# PGTNX02_vca.net
KiCad netlist of a schematic drawn in EAGLE
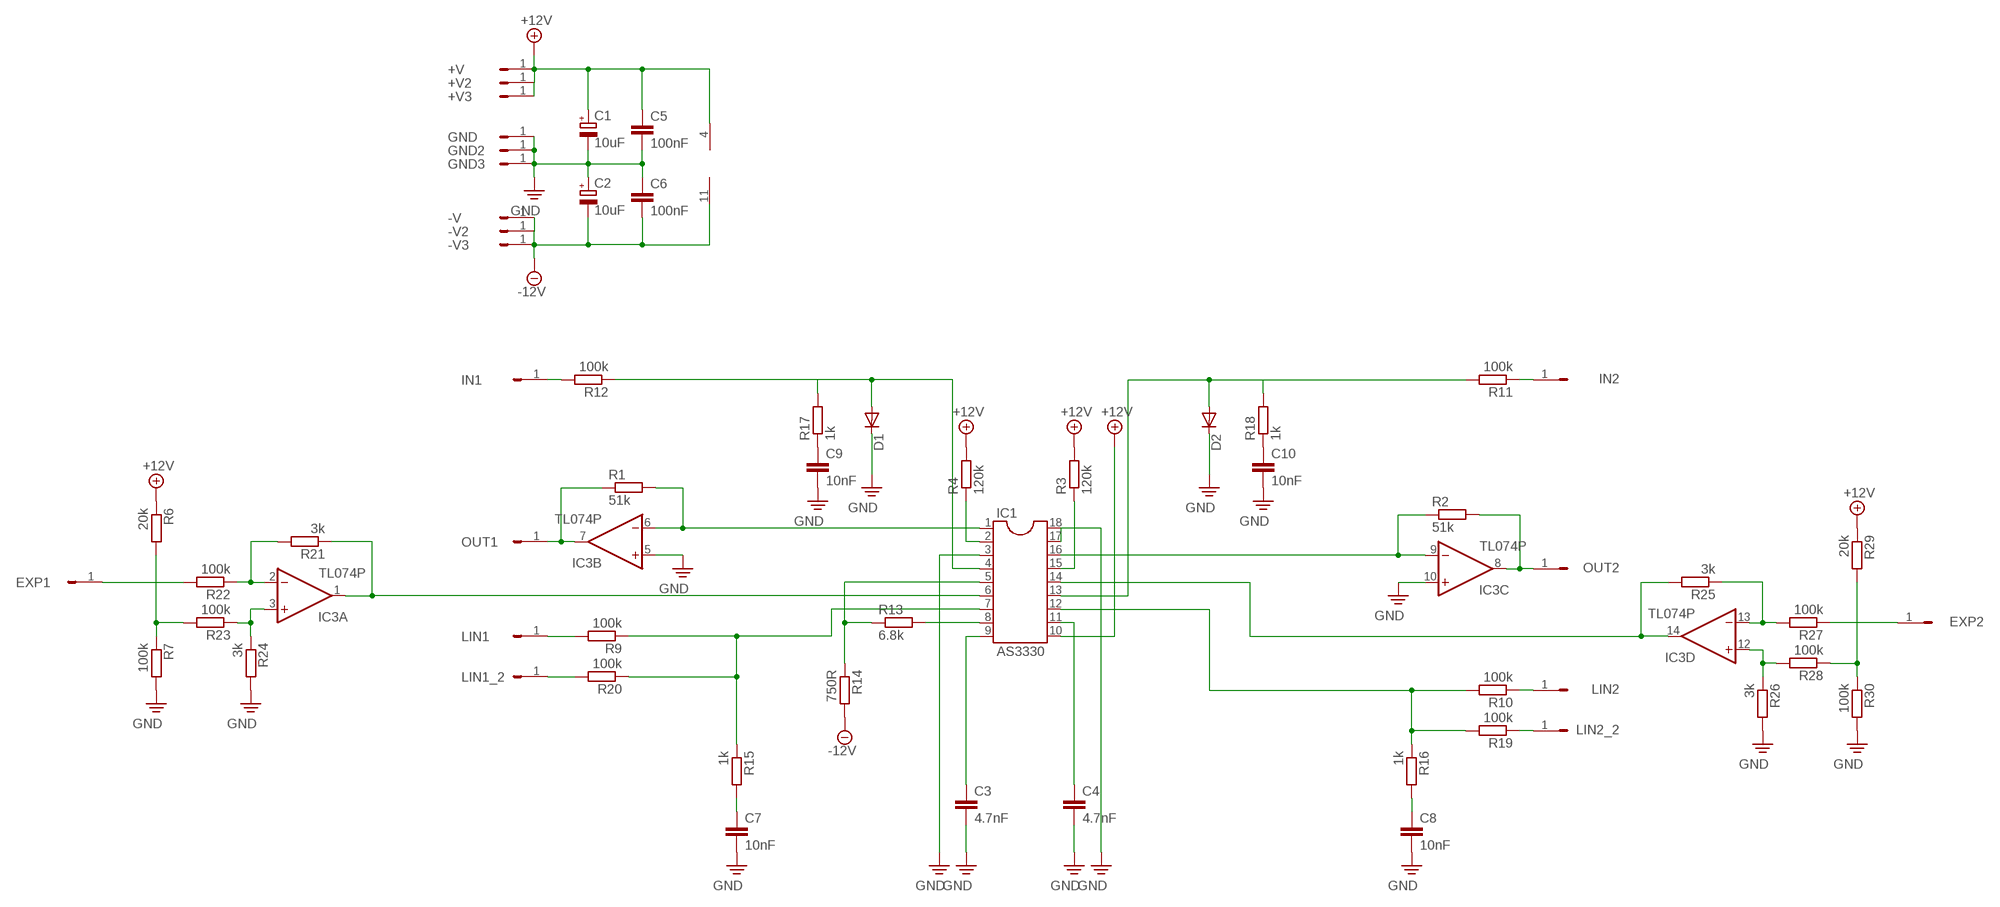
[diagram p0: schematic, sheet 1]

(export (version "E")
  (design (tool "Eeschema 10.0.6"))
  (components
    (comp (ref "+V")
      (value "HEADER/MALE/01")
      (footprint "eagle-import:HEADER_MALE_01")
      (fields (field (name "SPICEPREFIX") "X"))
      (libsource (lib "eagle-import") (part "HEADER/MALE/01"))
    )
    (comp (ref "+V2")
      (value "HEADER/MALE/01")
      (footprint "eagle-import:HEADER_MALE_01")
      (fields (field (name "SPICEPREFIX") "X"))
      (libsource (lib "eagle-import") (part "HEADER/MALE/01"))
    )
    (comp (ref "+V3")
      (value "HEADER/MALE/01")
      (footprint "eagle-import:HEADER_MALE_01")
      (fields (field (name "SPICEPREFIX") "X"))
      (libsource (lib "eagle-import") (part "HEADER/MALE/01"))
    )
    (comp (ref "-V")
      (value "HEADER/MALE/01")
      (footprint "eagle-import:HEADER_MALE_01")
      (fields (field (name "SPICEPREFIX") "X"))
      (libsource (lib "eagle-import") (part "HEADER/MALE/01"))
    )
    (comp (ref "-V2")
      (value "HEADER/MALE/01")
      (footprint "eagle-import:HEADER_MALE_01")
      (fields (field (name "SPICEPREFIX") "X"))
      (libsource (lib "eagle-import") (part "HEADER/MALE/01"))
    )
    (comp (ref "-V3")
      (value "HEADER/MALE/01")
      (footprint "eagle-import:HEADER_MALE_01")
      (fields (field (name "SPICEPREFIX") "X"))
      (libsource (lib "eagle-import") (part "HEADER/MALE/01"))
    )
    (comp (ref "C1")
      (value "10uF")
      (footprint "eagle-import:E2,5-6")
      (fields (field (name "SPICEPREFIX") "C"))
      (libsource (lib "eagle-import") (part "CAPACITOR/POLARIZEDE2.5-6"))
    )
    (comp (ref "C2")
      (value "10uF")
      (footprint "eagle-import:E2,5-6")
      (fields (field (name "SPICEPREFIX") "C"))
      (libsource (lib "eagle-import") (part "CAPACITOR/POLARIZEDE2.5-6"))
    )
    (comp (ref "C3")
      (value "4.7nF")
      (footprint "eagle-import:CERAMICDISC_5")
      (libsource (lib "eagle-import") (part "CAPACITORCERAMICDISC/5"))
    )
    (comp (ref "C4")
      (value "4.7nF")
      (footprint "eagle-import:CERAMICDISC_5")
      (libsource (lib "eagle-import") (part "CAPACITORCERAMICDISC/5"))
    )
    (comp (ref "C5")
      (value "100nF")
      (footprint "eagle-import:CERAMICDISC_5")
      (libsource (lib "eagle-import") (part "CAPACITORCERAMICDISC/5"))
    )
    (comp (ref "C6")
      (value "100nF")
      (footprint "eagle-import:CERAMICDISC_5")
      (libsource (lib "eagle-import") (part "CAPACITORCERAMICDISC/5"))
    )
    (comp (ref "C7")
      (value "10nF")
      (footprint "eagle-import:CERAMICDISC_5")
      (libsource (lib "eagle-import") (part "CAPACITORCERAMICDISC/5"))
    )
    (comp (ref "C8")
      (value "10nF")
      (footprint "eagle-import:CERAMICDISC_5")
      (libsource (lib "eagle-import") (part "CAPACITORCERAMICDISC/5"))
    )
    (comp (ref "C9")
      (value "10nF")
      (footprint "eagle-import:CERAMICDISC_5")
      (libsource (lib "eagle-import") (part "CAPACITORCERAMICDISC/5"))
    )
    (comp (ref "C10")
      (value "10nF")
      (footprint "eagle-import:CERAMICDISC_5")
      (libsource (lib "eagle-import") (part "CAPACITORCERAMICDISC/5"))
    )
    (comp (ref "D1")
      (value "1N4148DO35-7")
      (footprint "eagle-import:DO35-7")
      (libsource (lib "eagle-import") (part "1N4148DO35-7"))
    )
    (comp (ref "D2")
      (value "1N4148DO35-7")
      (footprint "eagle-import:DO35-7")
      (libsource (lib "eagle-import") (part "1N4148DO35-7"))
    )
    (comp (ref "EXP1")
      (value "HEADER/MALE/01")
      (footprint "eagle-import:HEADER_MALE_01")
      (libsource (lib "eagle-import") (part "HEADER/MALE/01"))
    )
    (comp (ref "EXP2")
      (value "HEADER/MALE/01")
      (footprint "eagle-import:HEADER_MALE_01")
      (libsource (lib "eagle-import") (part "HEADER/MALE/01"))
    )
    (comp (ref "GND")
      (value "HEADER/MALE/01")
      (footprint "eagle-import:HEADER_MALE_01")
      (fields (field (name "SPICEPREFIX") "X"))
      (libsource (lib "eagle-import") (part "HEADER/MALE/01"))
    )
    (comp (ref "GND2")
      (value "HEADER/MALE/01")
      (footprint "eagle-import:HEADER_MALE_01")
      (fields (field (name "SPICEPREFIX") "X"))
      (libsource (lib "eagle-import") (part "HEADER/MALE/01"))
    )
    (comp (ref "GND3")
      (value "HEADER/MALE/01")
      (footprint "eagle-import:HEADER_MALE_01")
      (fields (field (name "SPICEPREFIX") "X"))
      (libsource (lib "eagle-import") (part "HEADER/MALE/01"))
    )
    (comp (ref "IC1")
      (value "AS3330")
      (footprint "eagle-import:DIL18")
      (libsource (lib "eagle-import") (part "DIL18"))
    )
    (comp (ref "IC3")
      (value "TL074P")
      (footprint "eagle-import:DIL14")
      (libsource (lib "eagle-import") (part "TL074P"))
    )
    (comp (ref "IN1")
      (value "HEADER/MALE/01")
      (footprint "eagle-import:HEADER_MALE_01")
      (libsource (lib "eagle-import") (part "HEADER/MALE/01"))
    )
    (comp (ref "IN2")
      (value "HEADER/MALE/01")
      (footprint "eagle-import:HEADER_MALE_01")
      (libsource (lib "eagle-import") (part "HEADER/MALE/01"))
    )
    (comp (ref "LIN1")
      (value "HEADER/MALE/01")
      (footprint "eagle-import:HEADER_MALE_01")
      (libsource (lib "eagle-import") (part "HEADER/MALE/01"))
    )
    (comp (ref "LIN1_2")
      (value "HEADER/MALE/01")
      (footprint "eagle-import:HEADER_MALE_01")
      (libsource (lib "eagle-import") (part "HEADER/MALE/01"))
    )
    (comp (ref "LIN2")
      (value "HEADER/MALE/01")
      (footprint "eagle-import:HEADER_MALE_01")
      (libsource (lib "eagle-import") (part "HEADER/MALE/01"))
    )
    (comp (ref "LIN2_2")
      (value "HEADER/MALE/01")
      (footprint "eagle-import:HEADER_MALE_01")
      (libsource (lib "eagle-import") (part "HEADER/MALE/01"))
    )
    (comp (ref "OUT1")
      (value "HEADER/MALE/01")
      (footprint "eagle-import:HEADER_MALE_01")
      (libsource (lib "eagle-import") (part "HEADER/MALE/01"))
    )
    (comp (ref "OUT2")
      (value "HEADER/MALE/01")
      (footprint "eagle-import:HEADER_MALE_01")
      (libsource (lib "eagle-import") (part "HEADER/MALE/01"))
    )
    (comp (ref "R1")
      (value "51k")
      (footprint "eagle-import:RESISTOR_7.5")
      (libsource (lib "eagle-import") (part "RESISTORRESISTOR/UPRIGHT/7.5"))
    )
    (comp (ref "R2")
      (value "51k")
      (footprint "eagle-import:RESISTOR_7.5")
      (libsource (lib "eagle-import") (part "RESISTORRESISTOR/UPRIGHT/7.5"))
    )
    (comp (ref "R3")
      (value "120k")
      (footprint "eagle-import:RESISTOR_7.5")
      (libsource (lib "eagle-import") (part "RESISTORRESISTOR/UPRIGHT/7.5"))
    )
    (comp (ref "R4")
      (value "120k")
      (footprint "eagle-import:RESISTOR_7.5")
      (libsource (lib "eagle-import") (part "RESISTORRESISTOR/UPRIGHT/7.5"))
    )
    (comp (ref "R6")
      (value "20k")
      (footprint "eagle-import:RESISTOR_7.5")
      (libsource (lib "eagle-import") (part "RESISTORRESISTOR/UPRIGHT/7.5"))
    )
    (comp (ref "R7")
      (value "100k")
      (footprint "eagle-import:RESISTOR_7.5")
      (libsource (lib "eagle-import") (part "RESISTORRESISTOR/UPRIGHT/7.5"))
    )
    (comp (ref "R9")
      (value "100k")
      (footprint "eagle-import:RESISTOR_7.5")
      (libsource (lib "eagle-import") (part "RESISTORRESISTOR/UPRIGHT/7.5"))
    )
    (comp (ref "R10")
      (value "100k")
      (footprint "eagle-import:RESISTOR_7.5")
      (libsource (lib "eagle-import") (part "RESISTORRESISTOR/UPRIGHT/7.5"))
    )
    (comp (ref "R11")
      (value "100k")
      (footprint "eagle-import:RESISTOR_7.5")
      (libsource (lib "eagle-import") (part "RESISTORRESISTOR/UPRIGHT/7.5"))
    )
    (comp (ref "R12")
      (value "100k")
      (footprint "eagle-import:RESISTOR_7.5")
      (libsource (lib "eagle-import") (part "RESISTORRESISTOR/UPRIGHT/7.5"))
    )
    (comp (ref "R13")
      (value "6.8k")
      (footprint "eagle-import:RESISTOR_7.5")
      (libsource (lib "eagle-import") (part "RESISTORRESISTOR/UPRIGHT/7.5"))
    )
    (comp (ref "R14")
      (value "750R")
      (footprint "eagle-import:RESISTOR_7.5")
      (libsource (lib "eagle-import") (part "RESISTORRESISTOR/UPRIGHT/7.5"))
    )
    (comp (ref "R15")
      (value "1k")
      (footprint "eagle-import:RESISTOR_7.5")
      (libsource (lib "eagle-import") (part "RESISTORRESISTOR/UPRIGHT/7.5"))
    )
    (comp (ref "R16")
      (value "1k")
      (footprint "eagle-import:RESISTOR_7.5")
      (libsource (lib "eagle-import") (part "RESISTORRESISTOR/UPRIGHT/7.5"))
    )
    (comp (ref "R17")
      (value "1k")
      (footprint "eagle-import:RESISTOR_7.5")
      (libsource (lib "eagle-import") (part "RESISTORRESISTOR/UPRIGHT/7.5"))
    )
    (comp (ref "R18")
      (value "1k")
      (footprint "eagle-import:RESISTOR_7.5")
      (libsource (lib "eagle-import") (part "RESISTORRESISTOR/UPRIGHT/7.5"))
    )
    (comp (ref "R19")
      (value "100k")
      (footprint "eagle-import:RESISTOR_7.5")
      (libsource (lib "eagle-import") (part "RESISTORRESISTOR/UPRIGHT/7.5"))
    )
    (comp (ref "R20")
      (value "100k")
      (footprint "eagle-import:RESISTOR_7.5")
      (libsource (lib "eagle-import") (part "RESISTORRESISTOR/UPRIGHT/7.5"))
    )
    (comp (ref "R21")
      (value "3k")
      (footprint "eagle-import:RESISTOR_7.5")
      (libsource (lib "eagle-import") (part "RESISTORRESISTOR/UPRIGHT/7.5"))
    )
    (comp (ref "R22")
      (value "100k")
      (footprint "eagle-import:RESISTOR_7.5")
      (libsource (lib "eagle-import") (part "RESISTORRESISTOR/UPRIGHT/7.5"))
    )
    (comp (ref "R23")
      (value "100k")
      (footprint "eagle-import:RESISTOR_7.5")
      (libsource (lib "eagle-import") (part "RESISTORRESISTOR/UPRIGHT/7.5"))
    )
    (comp (ref "R24")
      (value "3k")
      (footprint "eagle-import:RESISTOR_7.5")
      (libsource (lib "eagle-import") (part "RESISTORRESISTOR/UPRIGHT/7.5"))
    )
    (comp (ref "R25")
      (value "3k")
      (footprint "eagle-import:RESISTOR_7.5")
      (libsource (lib "eagle-import") (part "RESISTORRESISTOR/UPRIGHT/7.5"))
    )
    (comp (ref "R26")
      (value "3k")
      (footprint "eagle-import:RESISTOR_7.5")
      (libsource (lib "eagle-import") (part "RESISTORRESISTOR/UPRIGHT/7.5"))
    )
    (comp (ref "R27")
      (value "100k")
      (footprint "eagle-import:RESISTOR_7.5")
      (libsource (lib "eagle-import") (part "RESISTORRESISTOR/UPRIGHT/7.5"))
    )
    (comp (ref "R28")
      (value "100k")
      (footprint "eagle-import:RESISTOR_7.5")
      (libsource (lib "eagle-import") (part "RESISTORRESISTOR/UPRIGHT/7.5"))
    )
    (comp (ref "R29")
      (value "20k")
      (footprint "eagle-import:RESISTOR_7.5")
      (libsource (lib "eagle-import") (part "RESISTORRESISTOR/UPRIGHT/7.5"))
    )
    (comp (ref "R30")
      (value "100k")
      (footprint "eagle-import:RESISTOR_7.5")
      (libsource (lib "eagle-import") (part "RESISTORRESISTOR/UPRIGHT/7.5"))
    )
  )
  (nets
    (net (code "1") (name "+12V") (class "Default")
      (node (ref "+V") (pin "1") (pinfunction "3_1") (pintype "passive"))
      (node (ref "+V2") (pin "1") (pinfunction "3_1") (pintype "passive"))
      (node (ref "+V3") (pin "1") (pinfunction "3_1") (pintype "passive"))
      (node (ref "C1") (pin "+") (pinfunction "+_+") (pintype "passive"))
      (node (ref "C5") (pin "1") (pinfunction "1_1") (pintype "passive"))
      (node (ref "IC1") (pin "10") (pinfunction "10_10") (pintype "passive"))
      (node (ref "IC3") (pin "4") (pinfunction "V+_4") (pintype "power_in"))
      (node (ref "R29") (pin "1") (pinfunction "1_1") (pintype "passive"))
      (node (ref "R3") (pin "2") (pinfunction "2_2") (pintype "passive"))
      (node (ref "R4") (pin "2") (pinfunction "2_2") (pintype "passive"))
      (node (ref "R6") (pin "1") (pinfunction "1_1") (pintype "passive"))
    )
    (net (code "2") (name "-12V") (class "Default")
      (node (ref "-V") (pin "1") (pinfunction "3_1") (pintype "passive"))
      (node (ref "-V2") (pin "1") (pinfunction "3_1") (pintype "passive"))
      (node (ref "-V3") (pin "1") (pinfunction "3_1") (pintype "passive"))
      (node (ref "C2") (pin "-") (pinfunction "-_-") (pintype "passive"))
      (node (ref "C6") (pin "2") (pinfunction "2_2") (pintype "passive"))
      (node (ref "IC3") (pin "11") (pinfunction "V-_11") (pintype "power_in"))
      (node (ref "R14") (pin "2") (pinfunction "2_2") (pintype "passive"))
    )
    (net (code "3") (name "GND") (class "Default")
      (node (ref "C1") (pin "-") (pinfunction "-_-") (pintype "passive"))
      (node (ref "C10") (pin "2") (pinfunction "2_2") (pintype "passive"))
      (node (ref "C2") (pin "+") (pinfunction "+_+") (pintype "passive"))
      (node (ref "C3") (pin "2") (pinfunction "2_2") (pintype "passive"))
      (node (ref "C4") (pin "2") (pinfunction "2_2") (pintype "passive"))
      (node (ref "C5") (pin "2") (pinfunction "2_2") (pintype "passive"))
      (node (ref "C6") (pin "1") (pinfunction "1_1") (pintype "passive"))
      (node (ref "C7") (pin "2") (pinfunction "2_2") (pintype "passive"))
      (node (ref "C8") (pin "2") (pinfunction "2_2") (pintype "passive"))
      (node (ref "C9") (pin "2") (pinfunction "2_2") (pintype "passive"))
      (node (ref "D1") (pin "C") (pinfunction "C_C") (pintype "passive"))
      (node (ref "D2") (pin "C") (pinfunction "C_C") (pintype "passive"))
      (node (ref "GND") (pin "1") (pinfunction "3_1") (pintype "passive"))
      (node (ref "GND2") (pin "1") (pinfunction "3_1") (pintype "passive"))
      (node (ref "GND3") (pin "1") (pinfunction "3_1") (pintype "passive"))
      (node (ref "IC1") (pin "17") (pinfunction "17_17") (pintype "passive"))
      (node (ref "IC1") (pin "18") (pinfunction "18_18") (pintype "passive"))
      (node (ref "IC1") (pin "3") (pinfunction "3_3") (pintype "passive"))
      (node (ref "IC3") (pin "10") (pinfunction "+IN_10") (pintype "input"))
      (node (ref "IC3") (pin "5") (pinfunction "+IN_5") (pintype "input"))
      (node (ref "R24") (pin "2") (pinfunction "2_2") (pintype "passive"))
      (node (ref "R26") (pin "2") (pinfunction "2_2") (pintype "passive"))
      (node (ref "R30") (pin "2") (pinfunction "2_2") (pintype "passive"))
      (node (ref "R7") (pin "2") (pinfunction "2_2") (pintype "passive"))
    )
    (net (code "4") (name "Net-(C3-Pad1)") (class "Default")
      (node (ref "C3") (pin "1") (pinfunction "1_1") (pintype "passive"))
      (node (ref "IC1") (pin "9") (pinfunction "9_9") (pintype "passive"))
    )
    (net (code "5") (name "Net-(C4-Pad1)") (class "Default")
      (node (ref "C4") (pin "1") (pinfunction "1_1") (pintype "passive"))
      (node (ref "IC1") (pin "11") (pinfunction "11_11") (pintype "passive"))
    )
    (net (code "6") (name "Net-(C7-Pad1)") (class "Default")
      (node (ref "C7") (pin "1") (pinfunction "1_1") (pintype "passive"))
      (node (ref "R15") (pin "2") (pinfunction "2_2") (pintype "passive"))
    )
    (net (code "7") (name "Net-(C8-Pad1)") (class "Default")
      (node (ref "C8") (pin "1") (pinfunction "1_1") (pintype "passive"))
      (node (ref "R16") (pin "2") (pinfunction "2_2") (pintype "passive"))
    )
    (net (code "8") (name "Net-(C9-Pad1)") (class "Default")
      (node (ref "C9") (pin "1") (pinfunction "1_1") (pintype "passive"))
      (node (ref "R17") (pin "1") (pinfunction "1_1") (pintype "passive"))
    )
    (net (code "9") (name "Net-(C10-Pad1)") (class "Default")
      (node (ref "C10") (pin "1") (pinfunction "1_1") (pintype "passive"))
      (node (ref "R18") (pin "1") (pinfunction "1_1") (pintype "passive"))
    )
    (net (code "10") (name "Net-(D1-PadA)") (class "Default")
      (node (ref "D1") (pin "A") (pinfunction "A_A") (pintype "passive"))
      (node (ref "IC1") (pin "4") (pinfunction "4_4") (pintype "passive"))
      (node (ref "R12") (pin "1") (pinfunction "1_1") (pintype "passive"))
      (node (ref "R17") (pin "2") (pinfunction "2_2") (pintype "passive"))
    )
    (net (code "11") (name "Net-(D2-PadA)") (class "Default")
      (node (ref "D2") (pin "A") (pinfunction "A_A") (pintype "passive"))
      (node (ref "IC1") (pin "13") (pinfunction "13_13") (pintype "passive"))
      (node (ref "R11") (pin "2") (pinfunction "2_2") (pintype "passive"))
      (node (ref "R18") (pin "2") (pinfunction "2_2") (pintype "passive"))
    )
    (net (code "12") (name "Net-(EXP1-3)") (class "Default")
      (node (ref "EXP1") (pin "1") (pinfunction "3_1") (pintype "passive"))
      (node (ref "R22") (pin "2") (pinfunction "2_2") (pintype "passive"))
    )
    (net (code "13") (name "Net-(EXP2-3)") (class "Default")
      (node (ref "EXP2") (pin "1") (pinfunction "3_1") (pintype "passive"))
      (node (ref "R27") (pin "1") (pinfunction "1_1") (pintype "passive"))
    )
    (net (code "14") (name "Net-(IC1-Pad2)") (class "Default")
      (node (ref "IC1") (pin "2") (pinfunction "2_2") (pintype "passive"))
      (node (ref "R4") (pin "1") (pinfunction "1_1") (pintype "passive"))
    )
    (net (code "15") (name "Net-(IC1-Pad5)") (class "Default")
      (node (ref "IC1") (pin "5") (pinfunction "5_5") (pintype "passive"))
      (node (ref "R13") (pin "1") (pinfunction "1_1") (pintype "passive"))
      (node (ref "R14") (pin "1") (pinfunction "1_1") (pintype "passive"))
    )
    (net (code "16") (name "Net-(IC1-Pad7)") (class "Default")
      (node (ref "IC1") (pin "7") (pinfunction "7_7") (pintype "passive"))
      (node (ref "R15") (pin "1") (pinfunction "1_1") (pintype "passive"))
      (node (ref "R20") (pin "1") (pinfunction "1_1") (pintype "passive"))
      (node (ref "R9") (pin "1") (pinfunction "1_1") (pintype "passive"))
    )
    (net (code "17") (name "Net-(IC1-Pad8)") (class "Default")
      (node (ref "IC1") (pin "8") (pinfunction "8_8") (pintype "passive"))
      (node (ref "R13") (pin "2") (pinfunction "2_2") (pintype "passive"))
    )
    (net (code "18") (name "Net-(IC1-Pad12)") (class "Default")
      (node (ref "IC1") (pin "12") (pinfunction "12_12") (pintype "passive"))
      (node (ref "R10") (pin "2") (pinfunction "2_2") (pintype "passive"))
      (node (ref "R16") (pin "1") (pinfunction "1_1") (pintype "passive"))
      (node (ref "R19") (pin "2") (pinfunction "2_2") (pintype "passive"))
    )
    (net (code "19") (name "Net-(IC1-Pad15)") (class "Default")
      (node (ref "IC1") (pin "15") (pinfunction "15_15") (pintype "passive"))
      (node (ref "R3") (pin "1") (pinfunction "1_1") (pintype "passive"))
    )
    (net (code "20") (name "Net-(IC3A-+IN)") (class "Default")
      (node (ref "IC3") (pin "3") (pinfunction "+IN_3") (pintype "input"))
      (node (ref "R23") (pin "1") (pinfunction "1_1") (pintype "passive"))
      (node (ref "R24") (pin "1") (pinfunction "1_1") (pintype "passive"))
    )
    (net (code "21") (name "Net-(IC3A--IN)") (class "Default")
      (node (ref "IC3") (pin "2") (pinfunction "-IN_2") (pintype "input"))
      (node (ref "R21") (pin "2") (pinfunction "2_2") (pintype "passive"))
      (node (ref "R22") (pin "1") (pinfunction "1_1") (pintype "passive"))
    )
    (net (code "22") (name "Net-(IC3A-OUT)") (class "Default")
      (node (ref "IC1") (pin "6") (pinfunction "6_6") (pintype "passive"))
      (node (ref "IC3") (pin "1") (pinfunction "OUT_1") (pintype "output"))
      (node (ref "R21") (pin "1") (pinfunction "1_1") (pintype "passive"))
    )
    (net (code "23") (name "Net-(IC3B--IN)") (class "Default")
      (node (ref "IC1") (pin "1") (pinfunction "1_1") (pintype "passive"))
      (node (ref "IC3") (pin "6") (pinfunction "-IN_6") (pintype "input"))
      (node (ref "R1") (pin "2") (pinfunction "2_2") (pintype "passive"))
    )
    (net (code "24") (name "Net-(IC3B-OUT)") (class "Default")
      (node (ref "IC3") (pin "7") (pinfunction "OUT_7") (pintype "output"))
      (node (ref "OUT1") (pin "1") (pinfunction "3_1") (pintype "passive"))
      (node (ref "R1") (pin "1") (pinfunction "1_1") (pintype "passive"))
    )
    (net (code "25") (name "Net-(IC3C--IN)") (class "Default")
      (node (ref "IC1") (pin "16") (pinfunction "16_16") (pintype "passive"))
      (node (ref "IC3") (pin "9") (pinfunction "-IN_9") (pintype "input"))
      (node (ref "R2") (pin "1") (pinfunction "1_1") (pintype "passive"))
    )
    (net (code "26") (name "Net-(IC3C-OUT)") (class "Default")
      (node (ref "IC3") (pin "8") (pinfunction "OUT_8") (pintype "output"))
      (node (ref "OUT2") (pin "1") (pinfunction "3_1") (pintype "passive"))
      (node (ref "R2") (pin "2") (pinfunction "2_2") (pintype "passive"))
    )
    (net (code "27") (name "Net-(IC3D-+IN)") (class "Default")
      (node (ref "IC3") (pin "12") (pinfunction "+IN_12") (pintype "input"))
      (node (ref "R26") (pin "1") (pinfunction "1_1") (pintype "passive"))
      (node (ref "R28") (pin "2") (pinfunction "2_2") (pintype "passive"))
    )
    (net (code "28") (name "Net-(IC3D--IN)") (class "Default")
      (node (ref "IC3") (pin "13") (pinfunction "-IN_13") (pintype "input"))
      (node (ref "R25") (pin "1") (pinfunction "1_1") (pintype "passive"))
      (node (ref "R27") (pin "2") (pinfunction "2_2") (pintype "passive"))
    )
    (net (code "29") (name "Net-(IC3D-OUT)") (class "Default")
      (node (ref "IC1") (pin "14") (pinfunction "14_14") (pintype "passive"))
      (node (ref "IC3") (pin "14") (pinfunction "OUT_14") (pintype "output"))
      (node (ref "R25") (pin "2") (pinfunction "2_2") (pintype "passive"))
    )
    (net (code "30") (name "Net-(IN1-3)") (class "Default")
      (node (ref "IN1") (pin "1") (pinfunction "3_1") (pintype "passive"))
      (node (ref "R12") (pin "2") (pinfunction "2_2") (pintype "passive"))
    )
    (net (code "31") (name "Net-(IN2-3)") (class "Default")
      (node (ref "IN2") (pin "1") (pinfunction "3_1") (pintype "passive"))
      (node (ref "R11") (pin "1") (pinfunction "1_1") (pintype "passive"))
    )
    (net (code "32") (name "Net-(LIN1-3)") (class "Default")
      (node (ref "LIN1") (pin "1") (pinfunction "3_1") (pintype "passive"))
      (node (ref "R9") (pin "2") (pinfunction "2_2") (pintype "passive"))
    )
    (net (code "33") (name "Net-(LIN1_2-3)") (class "Default")
      (node (ref "LIN1_2") (pin "1") (pinfunction "3_1") (pintype "passive"))
      (node (ref "R20") (pin "2") (pinfunction "2_2") (pintype "passive"))
    )
    (net (code "34") (name "Net-(LIN2-3)") (class "Default")
      (node (ref "LIN2") (pin "1") (pinfunction "3_1") (pintype "passive"))
      (node (ref "R10") (pin "1") (pinfunction "1_1") (pintype "passive"))
    )
    (net (code "35") (name "Net-(LIN2_2-3)") (class "Default")
      (node (ref "LIN2_2") (pin "1") (pinfunction "3_1") (pintype "passive"))
      (node (ref "R19") (pin "1") (pinfunction "1_1") (pintype "passive"))
    )
    (net (code "36") (name "Net-(R23-Pad2)") (class "Default")
      (node (ref "R23") (pin "2") (pinfunction "2_2") (pintype "passive"))
      (node (ref "R6") (pin "2") (pinfunction "2_2") (pintype "passive"))
      (node (ref "R7") (pin "1") (pinfunction "1_1") (pintype "passive"))
    )
    (net (code "37") (name "Net-(R28-Pad1)") (class "Default")
      (node (ref "R28") (pin "1") (pinfunction "1_1") (pintype "passive"))
      (node (ref "R29") (pin "2") (pinfunction "2_2") (pintype "passive"))
      (node (ref "R30") (pin "1") (pinfunction "1_1") (pintype "passive"))
    )
  )
)
